# DE-180824_1.net
KiCad netlist of a schematic drawn in Altium Designer
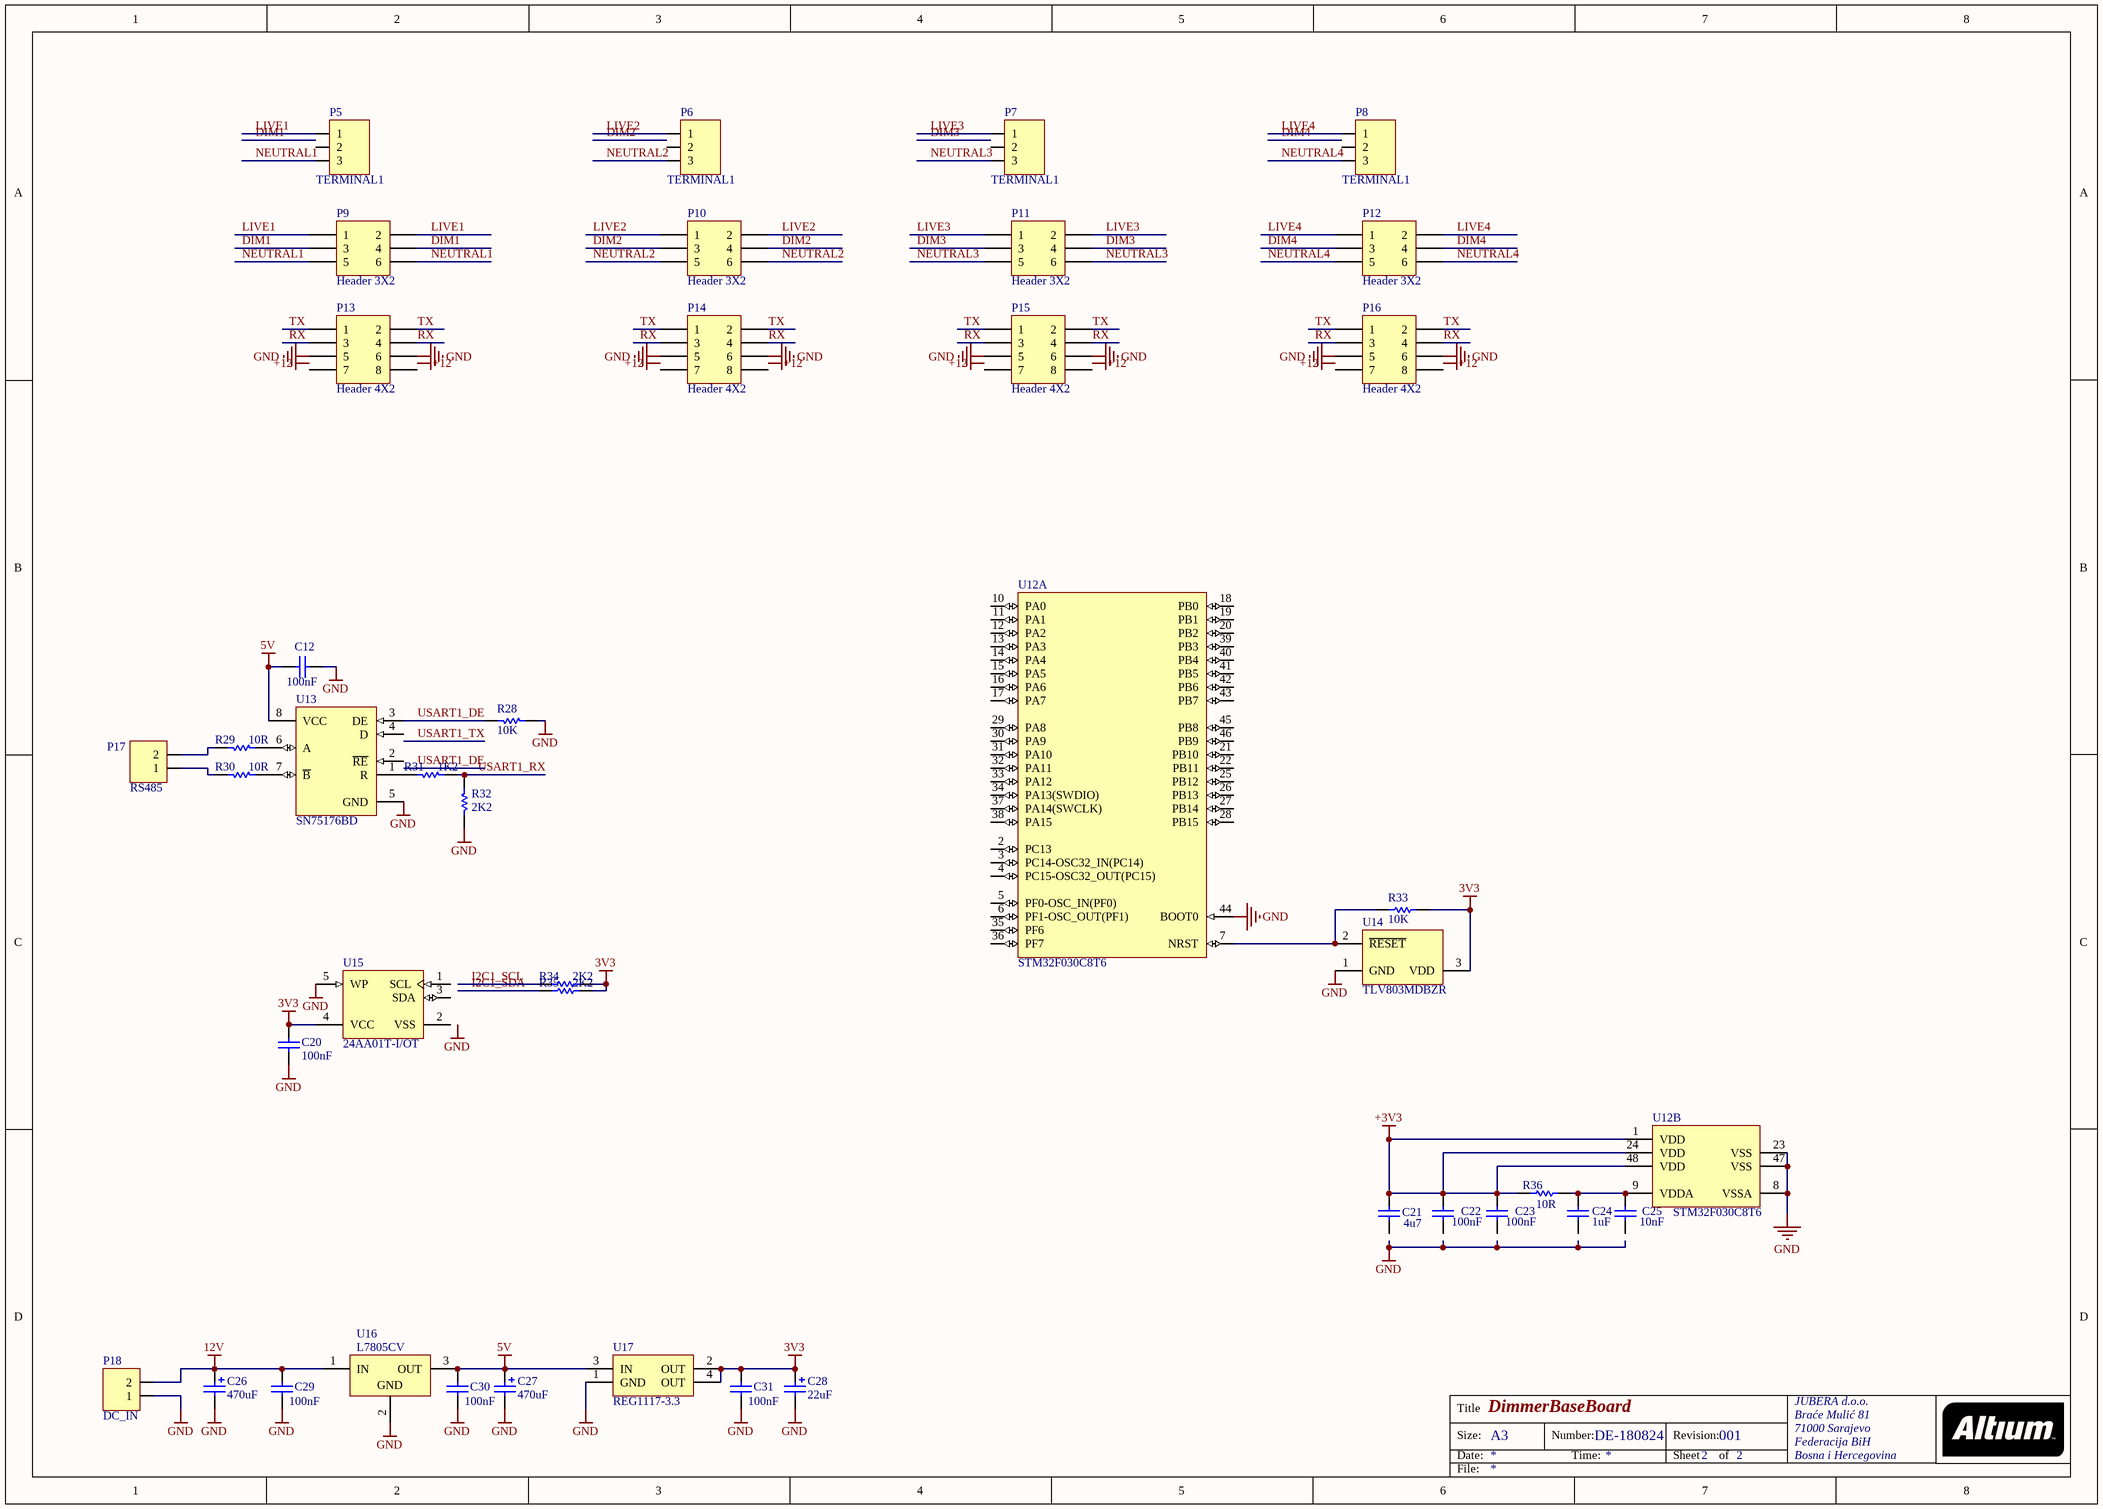
[diagram p0: DE-180824_1.SchDoc]

(export (version "E")
  (design (tool "Eeschema 10.0.6"))
  (components
    (comp (ref "C12")
      (value "100nF")
      (footprint "0603")
      (description "Ceramic Chip Capacitor - Standard")
      (fields (field (name "PUBLISHER") "Altium Limited"))
      (libsource (lib "DE-220817") (part "C0603"))
    )
    (comp (ref "C20")
      (value "100nF")
      (footprint "0603")
      (description "Ceramic Chip Capacitor - Standard")
      (fields (field (name "Comment") "C0603") (field (name "PUBLISHER") "Altium Limited"))
      (libsource (lib "DE-120824") (part "C0603"))
    )
    (comp (ref "C21")
      (value "4u7")
      (footprint "0805")
      (description "Ceramic Chip Capacitor - Standard")
      (fields (field (name "PUBLISHER") "Altium Limited"))
      (libsource (lib "KEMET Chip Capacitor") (part "C0805"))
    )
    (comp (ref "C22")
      (value "100nF")
      (footprint "0603")
      (description "Ceramic Chip Capacitor - Standard")
      (fields (field (name "PUBLISHER") "Altium Limited"))
      (libsource (lib "KEMET Chip Capacitor") (part "C0603"))
    )
    (comp (ref "C23")
      (value "100nF")
      (footprint "0603")
      (description "Ceramic Chip Capacitor - Standard")
      (fields (field (name "PUBLISHER") "Altium Limited"))
      (libsource (lib "KEMET Chip Capacitor") (part "C0603"))
    )
    (comp (ref "C24")
      (value "1uF")
      (footprint "0603")
      (description "Ceramic Chip Capacitor - Standard")
      (fields (field (name "PUBLISHER") "Altium Limited"))
      (libsource (lib "KEMET Chip Capacitor") (part "C0603"))
    )
    (comp (ref "C25")
      (value "10nF")
      (footprint "0603")
      (description "Ceramic Chip Capacitor - Standard")
      (fields (field (name "PUBLISHER") "Altium Limited"))
      (libsource (lib "KEMET Chip Capacitor") (part "C0603"))
    )
    (comp (ref "C26")
      (value "470uF")
      (footprint "CAPPR5-10X12.5")
      (description "Aluminum Electrolytic Capacitor, Radial Style with Long Leads: 470uF, 25V")
      (fields (field (name "PUBLISHER") "Altium Limited"))
      (libsource (lib "DE-010824") (part "EKA00DC347E00"))
    )
    (comp (ref "C27")
      (value "470uF")
      (footprint "CAPPR5-10X12.5")
      (description "Aluminum Electrolytic Capacitor, Radial Style with Long Leads: 470uF, 25V")
      (fields (field (name "PUBLISHER") "Altium Limited"))
      (libsource (lib "DE-010824") (part "EKA00DC347E00"))
    )
    (comp (ref "C28")
      (value "22uF")
      (footprint "CAPPR2-5X11")
      (description "Aluminum Electrolytic Capacitor, Radial Style with Long Leads: 47uF, 35V")
      (fields (field (name "PUBLISHER") "Altium Limited"))
      (libsource (lib "DE-010824") (part "EKA00AA247F00"))
    )
    (comp (ref "C29")
      (value "100nF")
      (footprint "0603")
      (description "Ceramic Chip Capacitor - Standard")
      (fields (field (name "PUBLISHER") "Altium Limited"))
      (libsource (lib "DE-220817") (part "C0603"))
    )
    (comp (ref "C30")
      (value "100nF")
      (footprint "0603")
      (description "Ceramic Chip Capacitor - Standard")
      (fields (field (name "PUBLISHER") "Altium Limited"))
      (libsource (lib "DE-220817") (part "C0603"))
    )
    (comp (ref "C31")
      (value "100nF")
      (footprint "0603")
      (description "Ceramic Chip Capacitor - Standard")
      (fields (field (name "PUBLISHER") "Altium Limited"))
      (libsource (lib "DE-220817") (part "C0603"))
    )
    (comp (ref "P5")
      (value "TERMINAL1")
      (footprint "3 PIN TERMINAL BLOCK  5mm")
      (description "3 pinski terminal blok konektor")
      (libsource (lib "DE-180824") (part "TERMINAL BLOK 3"))
    )
    (comp (ref "P6")
      (value "TERMINAL1")
      (footprint "3 PIN TERMINAL BLOCK  5mm")
      (description "3 pinski terminal blok konektor")
      (libsource (lib "DE-180824") (part "TERMINAL BLOK 3"))
    )
    (comp (ref "P7")
      (value "TERMINAL1")
      (footprint "3 PIN TERMINAL BLOCK  5mm")
      (description "3 pinski terminal blok konektor")
      (libsource (lib "DE-180824") (part "TERMINAL BLOK 3"))
    )
    (comp (ref "P8")
      (value "TERMINAL1")
      (footprint "3 PIN TERMINAL BLOCK  5mm")
      (description "3 pinski terminal blok konektor")
      (libsource (lib "DE-180824") (part "TERMINAL BLOK 3"))
    )
    (comp (ref "P9")
      (value "Header 3X2")
      (footprint "HDR2X3")
      (description "Header, 3-Pin, Dual row")
      (fields (field (name "PUBLISHER") "Altium Limited"))
      (libsource (lib "Miscellaneous Connectors") (part "Header 3X2"))
    )
    (comp (ref "P10")
      (value "Header 3X2")
      (footprint "HDR2X3")
      (description "Header, 3-Pin, Dual row")
      (fields (field (name "PUBLISHER") "Altium Limited"))
      (libsource (lib "Miscellaneous Connectors") (part "Header 3X2"))
    )
    (comp (ref "P11")
      (value "Header 3X2")
      (footprint "HDR2X3")
      (description "Header, 3-Pin, Dual row")
      (fields (field (name "PUBLISHER") "Altium Limited"))
      (libsource (lib "Miscellaneous Connectors") (part "Header 3X2"))
    )
    (comp (ref "P12")
      (value "Header 3X2")
      (footprint "HDR2X3")
      (description "Header, 3-Pin, Dual row")
      (fields (field (name "PUBLISHER") "Altium Limited"))
      (libsource (lib "Miscellaneous Connectors") (part "Header 3X2"))
    )
    (comp (ref "P13")
      (value "Header 4X2")
      (footprint "HDR2X4")
      (description "Header, 4-Pin, Dual row")
      (fields (field (name "PUBLISHER") "Altium Limited"))
      (libsource (lib "Miscellaneous Connectors") (part "Header 4X2"))
    )
    (comp (ref "P14")
      (value "Header 4X2")
      (footprint "HDR2X4")
      (description "Header, 4-Pin, Dual row")
      (fields (field (name "PUBLISHER") "Altium Limited"))
      (libsource (lib "Miscellaneous Connectors") (part "Header 4X2"))
    )
    (comp (ref "P15")
      (value "Header 4X2")
      (footprint "HDR2X4")
      (description "Header, 4-Pin, Dual row")
      (fields (field (name "PUBLISHER") "Altium Limited"))
      (libsource (lib "Miscellaneous Connectors") (part "Header 4X2"))
    )
    (comp (ref "P16")
      (value "Header 4X2")
      (footprint "HDR2X4")
      (description "Header, 4-Pin, Dual row")
      (fields (field (name "PUBLISHER") "Altium Limited"))
      (libsource (lib "Miscellaneous Connectors") (part "Header 4X2"))
    )
    (comp (ref "P17")
      (value "RS485")
      (footprint "TERMINAL BLOK 2")
      (description "Terminal blok konektor 3,5 mm")
      (libsource (lib "DE-120824") (part "TERMINAL BLOK 2"))
    )
    (comp (ref "P18")
      (value "DC_IN")
      (footprint "TERMINAL BLOK 2")
      (description "Terminal blok konektor 3,5 mm")
      (libsource (lib "DE-010824") (part "TERMINAL BLOK 2"))
    )
    (comp (ref "R28")
      (value "10K")
      (footprint "ERA-0603")
      (fields (field (name "PUBLISHER") "Altium Limited"))
      (libsource (lib "DE-220817") (part "ERAV"))
    )
    (comp (ref "R29")
      (value "10R")
      (footprint "ERA-0603")
      (fields (field (name "PUBLISHER") "Altium Limited"))
      (libsource (lib "DE-220817") (part "ERAV"))
    )
    (comp (ref "R30")
      (value "10R")
      (footprint "ERA-0603")
      (fields (field (name "PUBLISHER") "Altium Limited"))
      (libsource (lib "DE-220817") (part "ERAV"))
    )
    (comp (ref "R31")
      (value "1K2")
      (footprint "ERA-0603")
      (fields (field (name "PUBLISHER") "Altium Limited"))
      (libsource (lib "DE-220817") (part "ERAV"))
    )
    (comp (ref "R32")
      (value "2K2")
      (footprint "ERA-0603")
      (fields (field (name "PUBLISHER") "Altium Limited"))
      (libsource (lib "DE-220817") (part "ERAV"))
    )
    (comp (ref "R33")
      (value "10K")
      (footprint "ERA-0603")
      (fields (field (name "PUBLISHER") "Altium Limited"))
      (libsource (lib "DE-120824") (part "ERA3Y"))
    )
    (comp (ref "R34")
      (value "2K2")
      (footprint "ERA-0603")
      (fields (field (name "PUBLISHER") "Altium Limited"))
      (libsource (lib "DE-120824") (part "ERA3Y"))
    )
    (comp (ref "R35")
      (value "2K2")
      (footprint "ERA-0603")
      (fields (field (name "PUBLISHER") "Altium Limited"))
      (libsource (lib "DE-120824") (part "ERA3Y"))
    )
    (comp (ref "R36")
      (value "10R")
      (footprint "ERA-0603")
      (fields (field (name "PUBLISHER") "Altium Limited"))
      (libsource (lib "DE-280817") (part "ERA6Y"))
    )
    (comp (ref "U12")
      (value "STM32F030C8T6")
      (footprint "STM-LQFP48_N")
      (libsource (lib "STMicroelectronics STM32 F0") (part "STM32F030C8T6"))
    )
    (comp (ref "U13")
      (value "SN75176BD")
      (footprint "D008_N")
      (description "Differential Bus Transceiver")
      (fields (field (name "PUBLISHER") "Altium Limited"))
      (libsource (lib "DE-010824") (part "SN75176BD"))
    )
    (comp (ref "U14")
      (value "TLV803MDBZR")
      (footprint "DBZ3_N")
      (fields (field (name "MANUFACTURER") "Texas Instruments"))
      (libsource (lib "TI Power Management Supervisor and Reset IC") (part "TLV803MDBZR"))
    )
    (comp (ref "U15")
      (value "24AA01T-I/OT")
      (footprint "SOT-23-OT5_N")
      (description "1Kbit, 400kHz, 1.8V, I2C Serial EEPROM, 5-Pin SOT-23, Industrial Temperature, Tape and Reel")
      (fields (field (name "PUBLISHER") "Altium Limited"))
      (libsource (lib "Microchip Memory I2C Serial EEPROM") (part "24AA01T-I/OT"))
    )
    (comp (ref "U16")
      (value "L7805CV")
      (footprint "TO220")
      (description "Positive Voltage Regulator, 5V, 3-Pin TO-220")
      (libsource (lib "DE-010824") (part "L7805CV"))
    )
    (comp (ref "U17")
      (value "REG1117-3.3")
      (footprint "ZZ311")
      (description "800mA and 1A Low Dropout Positive Regulator 2.85V, 3.3V, 5V, and Adjustable")
      (fields (field (name "PUBLISHER") "Altium Limited"))
      (libsource (lib "DE-010824") (part "REG1117-3.3"))
    )
  )
  (nets
    (net (code "1") (name "+3V3") (class "Default")
      (node (ref "C21") (pin "1") (pinfunction "1_1") (pintype "passive"))
      (node (ref "C22") (pin "1") (pinfunction "1_1") (pintype "passive"))
      (node (ref "C23") (pin "1") (pinfunction "1_1") (pintype "passive"))
      (node (ref "R36") (pin "2") (pinfunction "2_2") (pintype "passive"))
      (node (ref "U12") (pin "1") (pinfunction "VDD_1") (pintype "power_in"))
      (node (ref "U12") (pin "24") (pinfunction "VDD_24") (pintype "power_in"))
      (node (ref "U12") (pin "48") (pinfunction "VDD_48") (pintype "power_in"))
    )
    (net (code "3") (name "/DIM1") (class "Default")
      (node (ref "P9") (pin "3") (pinfunction "3_3") (pintype "passive"))
      (node (ref "P9") (pin "4") (pinfunction "4_4") (pintype "passive"))
    )
    (net (code "4") (name "/DIM2") (class "Default")
      (node (ref "P10") (pin "3") (pinfunction "3_3") (pintype "passive"))
      (node (ref "P10") (pin "4") (pinfunction "4_4") (pintype "passive"))
    )
    (net (code "5") (name "/DIM3") (class "Default")
      (node (ref "P11") (pin "3") (pinfunction "3_3") (pintype "passive"))
      (node (ref "P11") (pin "4") (pinfunction "4_4") (pintype "passive"))
    )
    (net (code "6") (name "/DIM4") (class "Default")
      (node (ref "P12") (pin "3") (pinfunction "3_3") (pintype "passive"))
      (node (ref "P12") (pin "4") (pinfunction "4_4") (pintype "passive"))
    )
    (net (code "7") (name "/I2C1_SCL") (class "Default")
      (node (ref "R34") (pin "1") (pinfunction "1_1") (pintype "passive"))
    )
    (net (code "8") (name "/I2C1_SDA") (class "Default")
      (node (ref "R35") (pin "1") (pinfunction "1_1") (pintype "passive"))
    )
    (net (code "9") (name "/LIVE1") (class "Default")
      (node (ref "P5") (pin "1") (pinfunction "1_1") (pintype "passive"))
      (node (ref "P9") (pin "1") (pinfunction "1_1") (pintype "passive"))
      (node (ref "P9") (pin "2") (pinfunction "2_2") (pintype "passive"))
    )
    (net (code "10") (name "/LIVE2") (class "Default")
      (node (ref "P10") (pin "1") (pinfunction "1_1") (pintype "passive"))
      (node (ref "P10") (pin "2") (pinfunction "2_2") (pintype "passive"))
      (node (ref "P6") (pin "1") (pinfunction "1_1") (pintype "passive"))
    )
    (net (code "11") (name "/LIVE3") (class "Default")
      (node (ref "P11") (pin "1") (pinfunction "1_1") (pintype "passive"))
      (node (ref "P11") (pin "2") (pinfunction "2_2") (pintype "passive"))
      (node (ref "P7") (pin "1") (pinfunction "1_1") (pintype "passive"))
    )
    (net (code "12") (name "/LIVE4") (class "Default")
      (node (ref "P12") (pin "1") (pinfunction "1_1") (pintype "passive"))
      (node (ref "P12") (pin "2") (pinfunction "2_2") (pintype "passive"))
      (node (ref "P8") (pin "1") (pinfunction "1_1") (pintype "passive"))
    )
    (net (code "13") (name "/NEUTRAL1") (class "Default")
      (node (ref "P5") (pin "3") (pinfunction "3_3") (pintype "passive"))
      (node (ref "P9") (pin "5") (pinfunction "5_5") (pintype "passive"))
      (node (ref "P9") (pin "6") (pinfunction "6_6") (pintype "passive"))
    )
    (net (code "14") (name "/NEUTRAL2") (class "Default")
      (node (ref "P10") (pin "5") (pinfunction "5_5") (pintype "passive"))
      (node (ref "P10") (pin "6") (pinfunction "6_6") (pintype "passive"))
      (node (ref "P6") (pin "3") (pinfunction "3_3") (pintype "passive"))
    )
    (net (code "15") (name "/NEUTRAL3") (class "Default")
      (node (ref "P11") (pin "5") (pinfunction "5_5") (pintype "passive"))
      (node (ref "P11") (pin "6") (pinfunction "6_6") (pintype "passive"))
      (node (ref "P7") (pin "3") (pinfunction "3_3") (pintype "passive"))
    )
    (net (code "16") (name "/NEUTRAL4") (class "Default")
      (node (ref "P12") (pin "5") (pinfunction "5_5") (pintype "passive"))
      (node (ref "P12") (pin "6") (pinfunction "6_6") (pintype "passive"))
      (node (ref "P8") (pin "3") (pinfunction "3_3") (pintype "passive"))
    )
    (net (code "17") (name "/RX") (class "Default")
      (node (ref "P13") (pin "3") (pinfunction "3_3") (pintype "passive"))
      (node (ref "P13") (pin "4") (pinfunction "4_4") (pintype "passive"))
      (node (ref "P14") (pin "3") (pinfunction "3_3") (pintype "passive"))
      (node (ref "P14") (pin "4") (pinfunction "4_4") (pintype "passive"))
      (node (ref "P15") (pin "3") (pinfunction "3_3") (pintype "passive"))
      (node (ref "P15") (pin "4") (pinfunction "4_4") (pintype "passive"))
      (node (ref "P16") (pin "3") (pinfunction "3_3") (pintype "passive"))
      (node (ref "P16") (pin "4") (pinfunction "4_4") (pintype "passive"))
    )
    (net (code "18") (name "/TX") (class "Default")
      (node (ref "P13") (pin "1") (pinfunction "1_1") (pintype "passive"))
      (node (ref "P13") (pin "2") (pinfunction "2_2") (pintype "passive"))
      (node (ref "P14") (pin "1") (pinfunction "1_1") (pintype "passive"))
      (node (ref "P14") (pin "2") (pinfunction "2_2") (pintype "passive"))
      (node (ref "P15") (pin "1") (pinfunction "1_1") (pintype "passive"))
      (node (ref "P15") (pin "2") (pinfunction "2_2") (pintype "passive"))
      (node (ref "P16") (pin "1") (pinfunction "1_1") (pintype "passive"))
      (node (ref "P16") (pin "2") (pinfunction "2_2") (pintype "passive"))
    )
    (net (code "19") (name "/USART1_DE") (class "Default")
      (node (ref "R28") (pin "2") (pinfunction "2_2") (pintype "passive"))
      (node (ref "U13") (pin "3") (pinfunction "DE_3") (pintype "input"))
    )
    (net (code "20") (name "/USART1_RX") (class "Default")
      (node (ref "R31") (pin "1") (pinfunction "1_1") (pintype "passive"))
      (node (ref "R32") (pin "1") (pinfunction "1_1") (pintype "passive"))
    )
    (net (code "22") (name "3V3") (class "Default")
      (node (ref "C20") (pin "2") (pinfunction "2_2") (pintype "passive"))
      (node (ref "C28") (pin "1") (pinfunction "1_1") (pintype "passive"))
      (node (ref "C31") (pin "2") (pinfunction "2_2") (pintype "passive"))
      (node (ref "R33") (pin "2") (pinfunction "2_2") (pintype "passive"))
      (node (ref "R34") (pin "2") (pinfunction "2_2") (pintype "passive"))
      (node (ref "R35") (pin "2") (pinfunction "2_2") (pintype "passive"))
      (node (ref "U14") (pin "3") (pinfunction "VDD_3") (pintype "power_in"))
      (node (ref "U15") (pin "4") (pinfunction "VCC_4") (pintype "power_in"))
      (node (ref "U17") (pin "2") (pinfunction "OUT_2") (pintype "power_in"))
      (node (ref "U17") (pin "4") (pinfunction "OUT_4") (pintype "power_in"))
    )
    (net (code "23") (name "5V") (class "Default")
      (node (ref "C12") (pin "1") (pinfunction "1_1") (pintype "passive"))
      (node (ref "C27") (pin "1") (pinfunction "1_1") (pintype "passive"))
      (node (ref "C30") (pin "2") (pinfunction "2_2") (pintype "passive"))
      (node (ref "U13") (pin "8") (pinfunction "VCC_8") (pintype "power_in"))
      (node (ref "U16") (pin "3") (pinfunction "OUT_3") (pintype "power_in"))
      (node (ref "U17") (pin "3") (pinfunction "IN_3") (pintype "power_in"))
    )
    (net (code "24") (name "12V") (class "Default")
      (node (ref "C26") (pin "1") (pinfunction "1_1") (pintype "passive"))
      (node (ref "C29") (pin "2") (pinfunction "2_2") (pintype "passive"))
      (node (ref "P18") (pin "2") (pinfunction "2_2") (pintype "passive"))
      (node (ref "U16") (pin "1") (pinfunction "IN_1") (pintype "power_in"))
    )
    (net (code "25") (name "GND") (class "Default")
      (node (ref "C12") (pin "2") (pinfunction "2_2") (pintype "passive"))
      (node (ref "C20") (pin "1") (pinfunction "1_1") (pintype "passive"))
      (node (ref "C26") (pin "2") (pinfunction "2_2") (pintype "passive"))
      (node (ref "C27") (pin "2") (pinfunction "2_2") (pintype "passive"))
      (node (ref "C28") (pin "2") (pinfunction "2_2") (pintype "passive"))
      (node (ref "C29") (pin "1") (pinfunction "1_1") (pintype "passive"))
      (node (ref "C30") (pin "1") (pinfunction "1_1") (pintype "passive"))
      (node (ref "C31") (pin "1") (pinfunction "1_1") (pintype "passive"))
      (node (ref "P13") (pin "5") (pinfunction "5_5") (pintype "passive"))
      (node (ref "P13") (pin "6") (pinfunction "6_6") (pintype "passive"))
      (node (ref "P14") (pin "5") (pinfunction "5_5") (pintype "passive"))
      (node (ref "P14") (pin "6") (pinfunction "6_6") (pintype "passive"))
      (node (ref "P15") (pin "5") (pinfunction "5_5") (pintype "passive"))
      (node (ref "P15") (pin "6") (pinfunction "6_6") (pintype "passive"))
      (node (ref "P16") (pin "5") (pinfunction "5_5") (pintype "passive"))
      (node (ref "P16") (pin "6") (pinfunction "6_6") (pintype "passive"))
      (node (ref "P18") (pin "1") (pinfunction "1_1") (pintype "passive"))
      (node (ref "R28") (pin "1") (pinfunction "1_1") (pintype "passive"))
      (node (ref "R32") (pin "2") (pinfunction "2_2") (pintype "passive"))
      (node (ref "U12") (pin "23") (pinfunction "VSS_23") (pintype "power_in"))
      (node (ref "U12") (pin "44") (pinfunction "BOOT0_44") (pintype "input"))
      (node (ref "U12") (pin "47") (pinfunction "VSS_47") (pintype "power_in"))
      (node (ref "U12") (pin "8") (pinfunction "VSSA_8") (pintype "power_in"))
      (node (ref "U13") (pin "5") (pinfunction "GND_5") (pintype "power_in"))
      (node (ref "U14") (pin "1") (pinfunction "GND_1") (pintype "power_in"))
      (node (ref "U15") (pin "5") (pinfunction "WP_5") (pintype "input"))
      (node (ref "U16") (pin "2") (pinfunction "GND_2") (pintype "power_in"))
      (node (ref "U17") (pin "1") (pinfunction "GND_1") (pintype "power_in"))
    )
    (net (code "26") (name "Net-(P17-Pad1)") (class "Default")
      (node (ref "P17") (pin "1") (pinfunction "1_1") (pintype "passive"))
      (node (ref "R30") (pin "1") (pinfunction "1_1") (pintype "passive"))
    )
    (net (code "27") (name "Net-(P17-Pad2)") (class "Default")
      (node (ref "P17") (pin "2") (pinfunction "2_2") (pintype "passive"))
      (node (ref "R29") (pin "1") (pinfunction "1_1") (pintype "passive"))
    )
    (net (code "28") (name "Net-(U12A-NRST)") (class "Default")
      (node (ref "R33") (pin "1") (pinfunction "1_1") (pintype "passive"))
      (node (ref "U12") (pin "7") (pinfunction "NRST_7") (pintype "bidirectional"))
      (node (ref "U14") (pin "2") (pinfunction "~{RESET}_2") (pintype "open_collector"))
    )
    (net (code "29") (name "Net-(U12B-VDDA)") (class "Default")
      (node (ref "C24") (pin "1") (pinfunction "1_1") (pintype "passive"))
      (node (ref "C25") (pin "1") (pinfunction "1_1") (pintype "passive"))
      (node (ref "R36") (pin "1") (pinfunction "1_1") (pintype "passive"))
      (node (ref "U12") (pin "9") (pinfunction "VDDA_9") (pintype "power_in"))
    )
    (net (code "30") (name "Net-(U13-A)") (class "Default")
      (node (ref "R29") (pin "2") (pinfunction "2_2") (pintype "passive"))
      (node (ref "U13") (pin "6") (pinfunction "A_6") (pintype "bidirectional"))
    )
    (net (code "31") (name "Net-(U13-R)") (class "Default")
      (node (ref "R31") (pin "2") (pinfunction "2_2") (pintype "passive"))
      (node (ref "U13") (pin "1") (pinfunction "R_1") (pintype "tri_state"))
    )
    (net (code "32") (name "Net-(U13-~{B})") (class "Default")
      (node (ref "R30") (pin "2") (pinfunction "2_2") (pintype "passive"))
      (node (ref "U13") (pin "7") (pinfunction "~{B}_7") (pintype "bidirectional"))
    )
    (net (code "33") (name "unconnected-(C21-Pad2)") (class "Default")
      (node (ref "C21") (pin "2") (pinfunction "2_2") (pintype "passive"))
    )
    (net (code "34") (name "unconnected-(C22-Pad2)") (class "Default")
      (node (ref "C22") (pin "2") (pinfunction "2_2") (pintype "passive"))
    )
    (net (code "35") (name "unconnected-(C23-Pad2)") (class "Default")
      (node (ref "C23") (pin "2") (pinfunction "2_2") (pintype "passive"))
    )
    (net (code "36") (name "unconnected-(C24-Pad2)") (class "Default")
      (node (ref "C24") (pin "2") (pinfunction "2_2") (pintype "passive"))
    )
    (net (code "37") (name "unconnected-(C25-Pad2)") (class "Default")
      (node (ref "C25") (pin "2") (pinfunction "2_2") (pintype "passive"))
    )
    (net (code "38") (name "unconnected-(P5-Pad2)") (class "Default")
      (node (ref "P5") (pin "2") (pinfunction "2_2") (pintype "passive"))
    )
    (net (code "39") (name "unconnected-(P6-Pad2)") (class "Default")
      (node (ref "P6") (pin "2") (pinfunction "2_2") (pintype "passive"))
    )
    (net (code "40") (name "unconnected-(P7-Pad2)") (class "Default")
      (node (ref "P7") (pin "2") (pinfunction "2_2") (pintype "passive"))
    )
    (net (code "41") (name "unconnected-(P8-Pad2)") (class "Default")
      (node (ref "P8") (pin "2") (pinfunction "2_2") (pintype "passive"))
    )
    (net (code "42") (name "unconnected-(P13-Pad7)") (class "Default")
      (node (ref "P13") (pin "7") (pinfunction "7_7") (pintype "passive"))
    )
    (net (code "43") (name "unconnected-(P13-Pad8)") (class "Default")
      (node (ref "P13") (pin "8") (pinfunction "8_8") (pintype "passive"))
    )
    (net (code "44") (name "unconnected-(P14-Pad7)") (class "Default")
      (node (ref "P14") (pin "7") (pinfunction "7_7") (pintype "passive"))
    )
    (net (code "45") (name "unconnected-(P14-Pad8)") (class "Default")
      (node (ref "P14") (pin "8") (pinfunction "8_8") (pintype "passive"))
    )
    (net (code "46") (name "unconnected-(P15-Pad7)") (class "Default")
      (node (ref "P15") (pin "7") (pinfunction "7_7") (pintype "passive"))
    )
    (net (code "47") (name "unconnected-(P15-Pad8)") (class "Default")
      (node (ref "P15") (pin "8") (pinfunction "8_8") (pintype "passive"))
    )
    (net (code "48") (name "unconnected-(P16-Pad7)") (class "Default")
      (node (ref "P16") (pin "7") (pinfunction "7_7") (pintype "passive"))
    )
    (net (code "49") (name "unconnected-(P16-Pad8)") (class "Default")
      (node (ref "P16") (pin "8") (pinfunction "8_8") (pintype "passive"))
    )
    (net (code "50") (name "unconnected-(U12A-PA0-Pad10)") (class "Default")
      (node (ref "U12") (pin "10") (pinfunction "PA0_10") (pintype "bidirectional"))
    )
    (net (code "51") (name "unconnected-(U12A-PA1-Pad11)") (class "Default")
      (node (ref "U12") (pin "11") (pinfunction "PA1_11") (pintype "bidirectional"))
    )
    (net (code "52") (name "unconnected-(U12A-PA2-Pad12)") (class "Default")
      (node (ref "U12") (pin "12") (pinfunction "PA2_12") (pintype "bidirectional"))
    )
    (net (code "53") (name "unconnected-(U12A-PA3-Pad13)") (class "Default")
      (node (ref "U12") (pin "13") (pinfunction "PA3_13") (pintype "bidirectional"))
    )
    (net (code "54") (name "unconnected-(U12A-PA4-Pad14)") (class "Default")
      (node (ref "U12") (pin "14") (pinfunction "PA4_14") (pintype "bidirectional"))
    )
    (net (code "55") (name "unconnected-(U12A-PA5-Pad15)") (class "Default")
      (node (ref "U12") (pin "15") (pinfunction "PA5_15") (pintype "bidirectional"))
    )
    (net (code "56") (name "unconnected-(U12A-PA6-Pad16)") (class "Default")
      (node (ref "U12") (pin "16") (pinfunction "PA6_16") (pintype "bidirectional"))
    )
    (net (code "57") (name "unconnected-(U12A-PA7-Pad17)") (class "Default")
      (node (ref "U12") (pin "17") (pinfunction "PA7_17") (pintype "bidirectional"))
    )
    (net (code "58") (name "unconnected-(U12A-PA8-Pad29)") (class "Default")
      (node (ref "U12") (pin "29") (pinfunction "PA8_29") (pintype "bidirectional"))
    )
    (net (code "59") (name "unconnected-(U12A-PA9-Pad30)") (class "Default")
      (node (ref "U12") (pin "30") (pinfunction "PA9_30") (pintype "bidirectional"))
    )
    (net (code "60") (name "unconnected-(U12A-PA10-Pad31)") (class "Default")
      (node (ref "U12") (pin "31") (pinfunction "PA10_31") (pintype "bidirectional"))
    )
    (net (code "61") (name "unconnected-(U12A-PA11-Pad32)") (class "Default")
      (node (ref "U12") (pin "32") (pinfunction "PA11_32") (pintype "bidirectional"))
    )
    (net (code "62") (name "unconnected-(U12A-PA12-Pad33)") (class "Default")
      (node (ref "U12") (pin "33") (pinfunction "PA12_33") (pintype "bidirectional"))
    )
    (net (code "63") (name "unconnected-(U12A-PA13(SWDIO)-Pad34)") (class "Default")
      (node (ref "U12") (pin "34") (pinfunction "PA13(SWDIO)_34") (pintype "bidirectional"))
    )
    (net (code "64") (name "unconnected-(U12A-PA14(SWCLK)-Pad37)") (class "Default")
      (node (ref "U12") (pin "37") (pinfunction "PA14(SWCLK)_37") (pintype "bidirectional"))
    )
    (net (code "65") (name "unconnected-(U12A-PA15-Pad38)") (class "Default")
      (node (ref "U12") (pin "38") (pinfunction "PA15_38") (pintype "bidirectional"))
    )
    (net (code "66") (name "unconnected-(U12A-PB0-Pad18)") (class "Default")
      (node (ref "U12") (pin "18") (pinfunction "PB0_18") (pintype "bidirectional"))
    )
    (net (code "67") (name "unconnected-(U12A-PB1-Pad19)") (class "Default")
      (node (ref "U12") (pin "19") (pinfunction "PB1_19") (pintype "bidirectional"))
    )
    (net (code "68") (name "unconnected-(U12A-PB2-Pad20)") (class "Default")
      (node (ref "U12") (pin "20") (pinfunction "PB2_20") (pintype "bidirectional"))
    )
    (net (code "69") (name "unconnected-(U12A-PB3-Pad39)") (class "Default")
      (node (ref "U12") (pin "39") (pinfunction "PB3_39") (pintype "bidirectional"))
    )
    (net (code "70") (name "unconnected-(U12A-PB4-Pad40)") (class "Default")
      (node (ref "U12") (pin "40") (pinfunction "PB4_40") (pintype "bidirectional"))
    )
    (net (code "71") (name "unconnected-(U12A-PB5-Pad41)") (class "Default")
      (node (ref "U12") (pin "41") (pinfunction "PB5_41") (pintype "bidirectional"))
    )
    (net (code "72") (name "unconnected-(U12A-PB6-Pad42)") (class "Default")
      (node (ref "U12") (pin "42") (pinfunction "PB6_42") (pintype "bidirectional"))
    )
    (net (code "73") (name "unconnected-(U12A-PB7-Pad43)") (class "Default")
      (node (ref "U12") (pin "43") (pinfunction "PB7_43") (pintype "bidirectional"))
    )
    (net (code "74") (name "unconnected-(U12A-PB8-Pad45)") (class "Default")
      (node (ref "U12") (pin "45") (pinfunction "PB8_45") (pintype "bidirectional"))
    )
    (net (code "75") (name "unconnected-(U12A-PB9-Pad46)") (class "Default")
      (node (ref "U12") (pin "46") (pinfunction "PB9_46") (pintype "bidirectional"))
    )
    (net (code "76") (name "unconnected-(U12A-PB10-Pad21)") (class "Default")
      (node (ref "U12") (pin "21") (pinfunction "PB10_21") (pintype "bidirectional"))
    )
    (net (code "77") (name "unconnected-(U12A-PB11-Pad22)") (class "Default")
      (node (ref "U12") (pin "22") (pinfunction "PB11_22") (pintype "bidirectional"))
    )
    (net (code "78") (name "unconnected-(U12A-PB12-Pad25)") (class "Default")
      (node (ref "U12") (pin "25") (pinfunction "PB12_25") (pintype "bidirectional"))
    )
    (net (code "79") (name "unconnected-(U12A-PB13-Pad26)") (class "Default")
      (node (ref "U12") (pin "26") (pinfunction "PB13_26") (pintype "bidirectional"))
    )
    (net (code "80") (name "unconnected-(U12A-PB14-Pad27)") (class "Default")
      (node (ref "U12") (pin "27") (pinfunction "PB14_27") (pintype "bidirectional"))
    )
    (net (code "81") (name "unconnected-(U12A-PB15-Pad28)") (class "Default")
      (node (ref "U12") (pin "28") (pinfunction "PB15_28") (pintype "bidirectional"))
    )
    (net (code "82") (name "unconnected-(U12A-PC13-Pad2)") (class "Default")
      (node (ref "U12") (pin "2") (pinfunction "PC13_2") (pintype "bidirectional"))
    )
    (net (code "83") (name "unconnected-(U12A-PC14-OSC32_IN(PC14)-Pad3)") (class "Default")
      (node (ref "U12") (pin "3") (pinfunction "PC14-OSC32_IN(PC14)_3") (pintype "bidirectional"))
    )
    (net (code "84") (name "unconnected-(U12A-PC15-OSC32_OUT(PC15)-Pad4)") (class "Default")
      (node (ref "U12") (pin "4") (pinfunction "PC15-OSC32_OUT(PC15)_4") (pintype "bidirectional"))
    )
    (net (code "85") (name "unconnected-(U12A-PF0-OSC_IN(PF0)-Pad5)") (class "Default")
      (node (ref "U12") (pin "5") (pinfunction "PF0-OSC_IN(PF0)_5") (pintype "bidirectional"))
    )
    (net (code "86") (name "unconnected-(U12A-PF1-OSC_OUT(PF1)-Pad6)") (class "Default")
      (node (ref "U12") (pin "6") (pinfunction "PF1-OSC_OUT(PF1)_6") (pintype "bidirectional"))
    )
    (net (code "87") (name "unconnected-(U12A-PF6-Pad35)") (class "Default")
      (node (ref "U12") (pin "35") (pinfunction "PF6_35") (pintype "bidirectional"))
    )
    (net (code "88") (name "unconnected-(U12A-PF7-Pad36)") (class "Default")
      (node (ref "U12") (pin "36") (pinfunction "PF7_36") (pintype "bidirectional"))
    )
    (net (code "89") (name "unconnected-(U13-D-Pad4)") (class "Default")
      (node (ref "U13") (pin "4") (pinfunction "D_4") (pintype "input"))
    )
    (net (code "90") (name "unconnected-(U13-~{RE}-Pad2)") (class "Default")
      (node (ref "U13") (pin "2") (pinfunction "~{RE}_2") (pintype "input"))
    )
    (net (code "91") (name "unconnected-(U15-SCL-Pad1)") (class "Default")
      (node (ref "U15") (pin "1") (pinfunction "SCL_1") (pintype "input"))
    )
    (net (code "92") (name "unconnected-(U15-SDA-Pad3)") (class "Default")
      (node (ref "U15") (pin "3") (pinfunction "SDA_3") (pintype "bidirectional"))
    )
    (net (code "93") (name "unconnected-(U15-VSS-Pad2)") (class "Default")
      (node (ref "U15") (pin "2") (pinfunction "VSS_2") (pintype "power_in"))
    )
  )
)
